# blinky.net
KiCad netlist of a schematic drawn in EAGLE
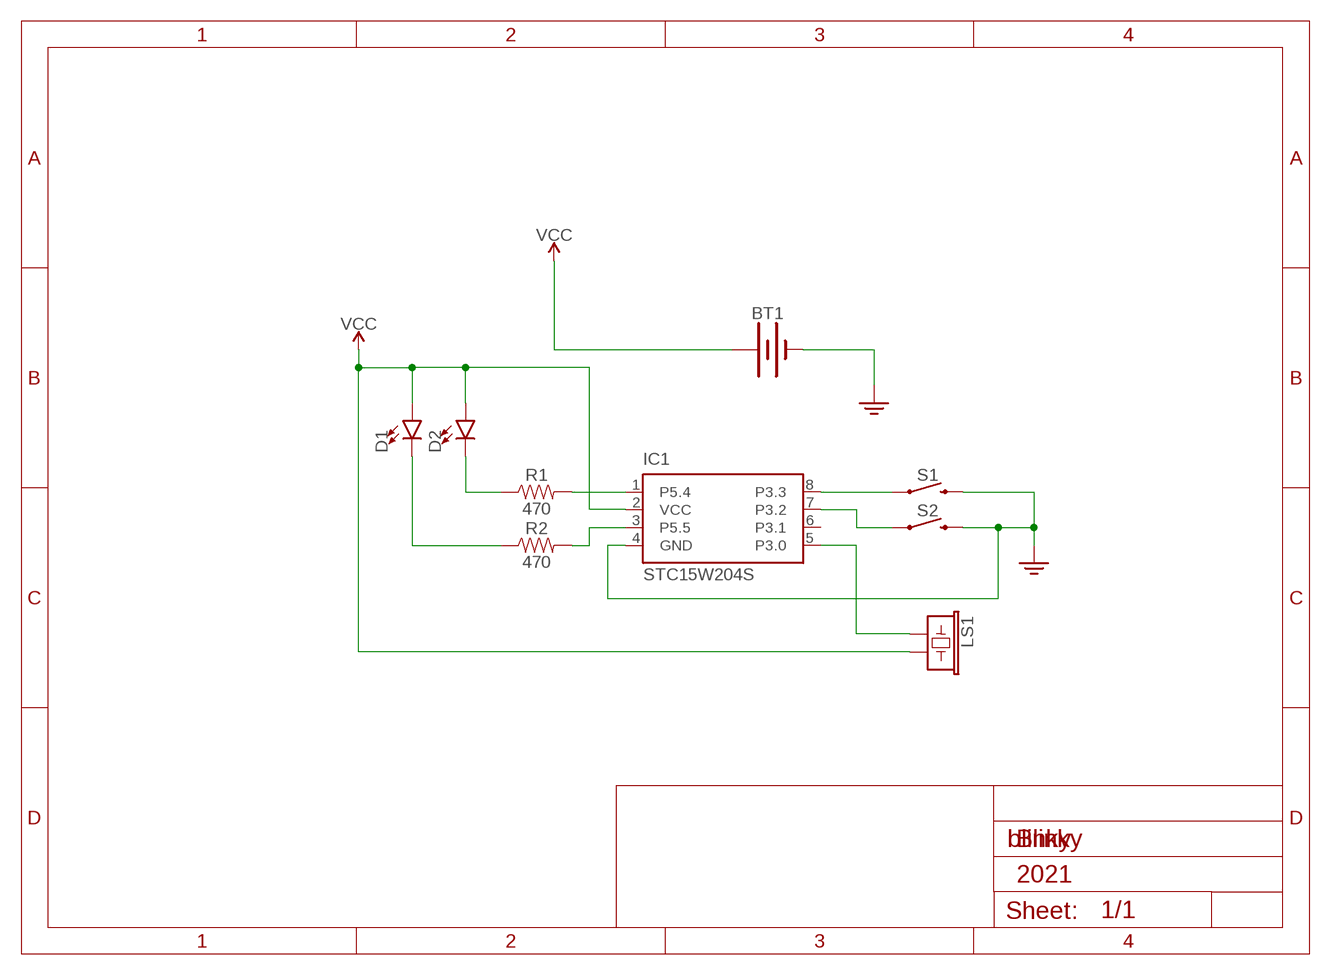
[diagram p0: schematic, sheet 1]

(export (version "E")
  (design (tool "Eeschema 10.0.6"))
  (components
    (comp (ref "BT1")
      (value "BATTERY-20MM_PTH")
      (footprint "eagle-import:BATTCOM_20MM_PTH")
      (libsource (lib "eagle-import") (part "BATTERY-20MM_PTH"))
    )
    (comp (ref "D1")
      (value "LED5MM")
      (footprint "eagle-import:LED_5MM")
      (libsource (lib "eagle-import") (part "LED5MM"))
    )
    (comp (ref "D2")
      (value "LED5MM")
      (footprint "eagle-import:LED_5MM")
      (libsource (lib "eagle-import") (part "LED5MM"))
    )
    (comp (ref "IC1")
      (value "STC15W204S")
      (footprint "eagle-import:SOP-08")
      (fields (field (name "MF") "TEXAS INSTRUMENT CONNECTORS") (field (name "MPN") "TPS77315DGK"))
      (libsource (lib "eagle-import") (part "TPS77315"))
    )
    (comp (ref "LS1")
      (value "BUZZER-PTH")
      (footprint "eagle-import:BUZZER-12MM")
      (libsource (lib "eagle-import") (part "BUZZER-PTH"))
    )
    (comp (ref "R1")
      (value "470")
      (footprint "eagle-import:AXIAL-0.3")
      (libsource (lib "eagle-import") (part "10KOHM-HORIZ-1/4W-1%"))
    )
    (comp (ref "R2")
      (value "470")
      (footprint "eagle-import:AXIAL-0.3")
      (libsource (lib "eagle-import") (part "10KOHM-HORIZ-1/4W-1%"))
    )
    (comp (ref "S1")
      (value "MOMENTARY-SWITCH-SPST-PTH-6.0MM")
      (footprint "eagle-import:TACTILE_SWITCH_PTH_6.0MM")
      (libsource (lib "eagle-import") (part "MOMENTARY-SWITCH-SPST-PTH-6.0MM"))
    )
    (comp (ref "S2")
      (value "MOMENTARY-SWITCH-SPST-PTH-6.0MM")
      (footprint "eagle-import:TACTILE_SWITCH_PTH_6.0MM")
      (libsource (lib "eagle-import") (part "MOMENTARY-SWITCH-SPST-PTH-6.0MM"))
    )
  )
  (nets
    (net (code "1") (name "GND2") (class "Default")
      (node (ref "BT1") (pin "2") (pinfunction "-_2") (pintype "power_in"))
      (node (ref "IC1") (pin "4") (pinfunction "GND_4") (pintype "power_in"))
      (node (ref "S1") (pin "3") (pinfunction "2_3") (pintype "passive"))
      (node (ref "S2") (pin "3") (pinfunction "2_3") (pintype "passive"))
    )
    (net (code "2") (name "Net-(D1-C)") (class "Default")
      (node (ref "D1") (pin "K") (pinfunction "C_K") (pintype "passive"))
      (node (ref "R2") (pin "P$1") (pinfunction "1_P$1") (pintype "passive"))
    )
    (net (code "3") (name "Net-(D2-C)") (class "Default")
      (node (ref "D2") (pin "K") (pinfunction "C_K") (pintype "passive"))
      (node (ref "R1") (pin "P$1") (pinfunction "1_P$1") (pintype "passive"))
    )
    (net (code "4") (name "Net-(IC1-P3.0)") (class "Default")
      (node (ref "IC1") (pin "5") (pinfunction "P3.0_5") (pintype "input"))
      (node (ref "LS1") (pin "+") (pinfunction "1_+") (pintype "passive"))
    )
    (net (code "5") (name "Net-(IC1-P3.2)") (class "Default")
      (node (ref "IC1") (pin "7") (pinfunction "P3.2_7") (pintype "output"))
      (node (ref "S2") (pin "1") (pinfunction "1_1") (pintype "passive"))
    )
    (net (code "6") (name "Net-(IC1-P3.3)") (class "Default")
      (node (ref "IC1") (pin "8") (pinfunction "P3.3_8") (pintype "passive"))
      (node (ref "S1") (pin "1") (pinfunction "1_1") (pintype "passive"))
    )
    (net (code "7") (name "Net-(IC1-P5.4)") (class "Default")
      (node (ref "IC1") (pin "1") (pinfunction "P5.4_1") (pintype "input"))
      (node (ref "R1") (pin "P$2") (pinfunction "2_P$2") (pintype "passive"))
    )
    (net (code "8") (name "Net-(IC1-P5.5)") (class "Default")
      (node (ref "IC1") (pin "3") (pinfunction "P5.5_3") (pintype "input"))
      (node (ref "R2") (pin "P$2") (pinfunction "2_P$2") (pintype "passive"))
    )
    (net (code "9") (name "VCC") (class "Default")
      (node (ref "BT1") (pin "1") (pinfunction "+_1") (pintype "power_in"))
      (node (ref "D1") (pin "A") (pinfunction "A_A") (pintype "passive"))
      (node (ref "D2") (pin "A") (pinfunction "A_A") (pintype "passive"))
      (node (ref "IC1") (pin "2") (pinfunction "VCC_2") (pintype "input"))
      (node (ref "LS1") (pin "-") (pinfunction "2_-") (pintype "passive"))
    )
    (net (code "10") (name "unconnected-(IC1-P3.1-Pad6)") (class "Default")
      (node (ref "IC1") (pin "6") (pinfunction "P3.1_6") (pintype "input"))
    )
  )
)
